# Microcontroller.net
KiCad netlist of a schematic drawn in Altium Designer
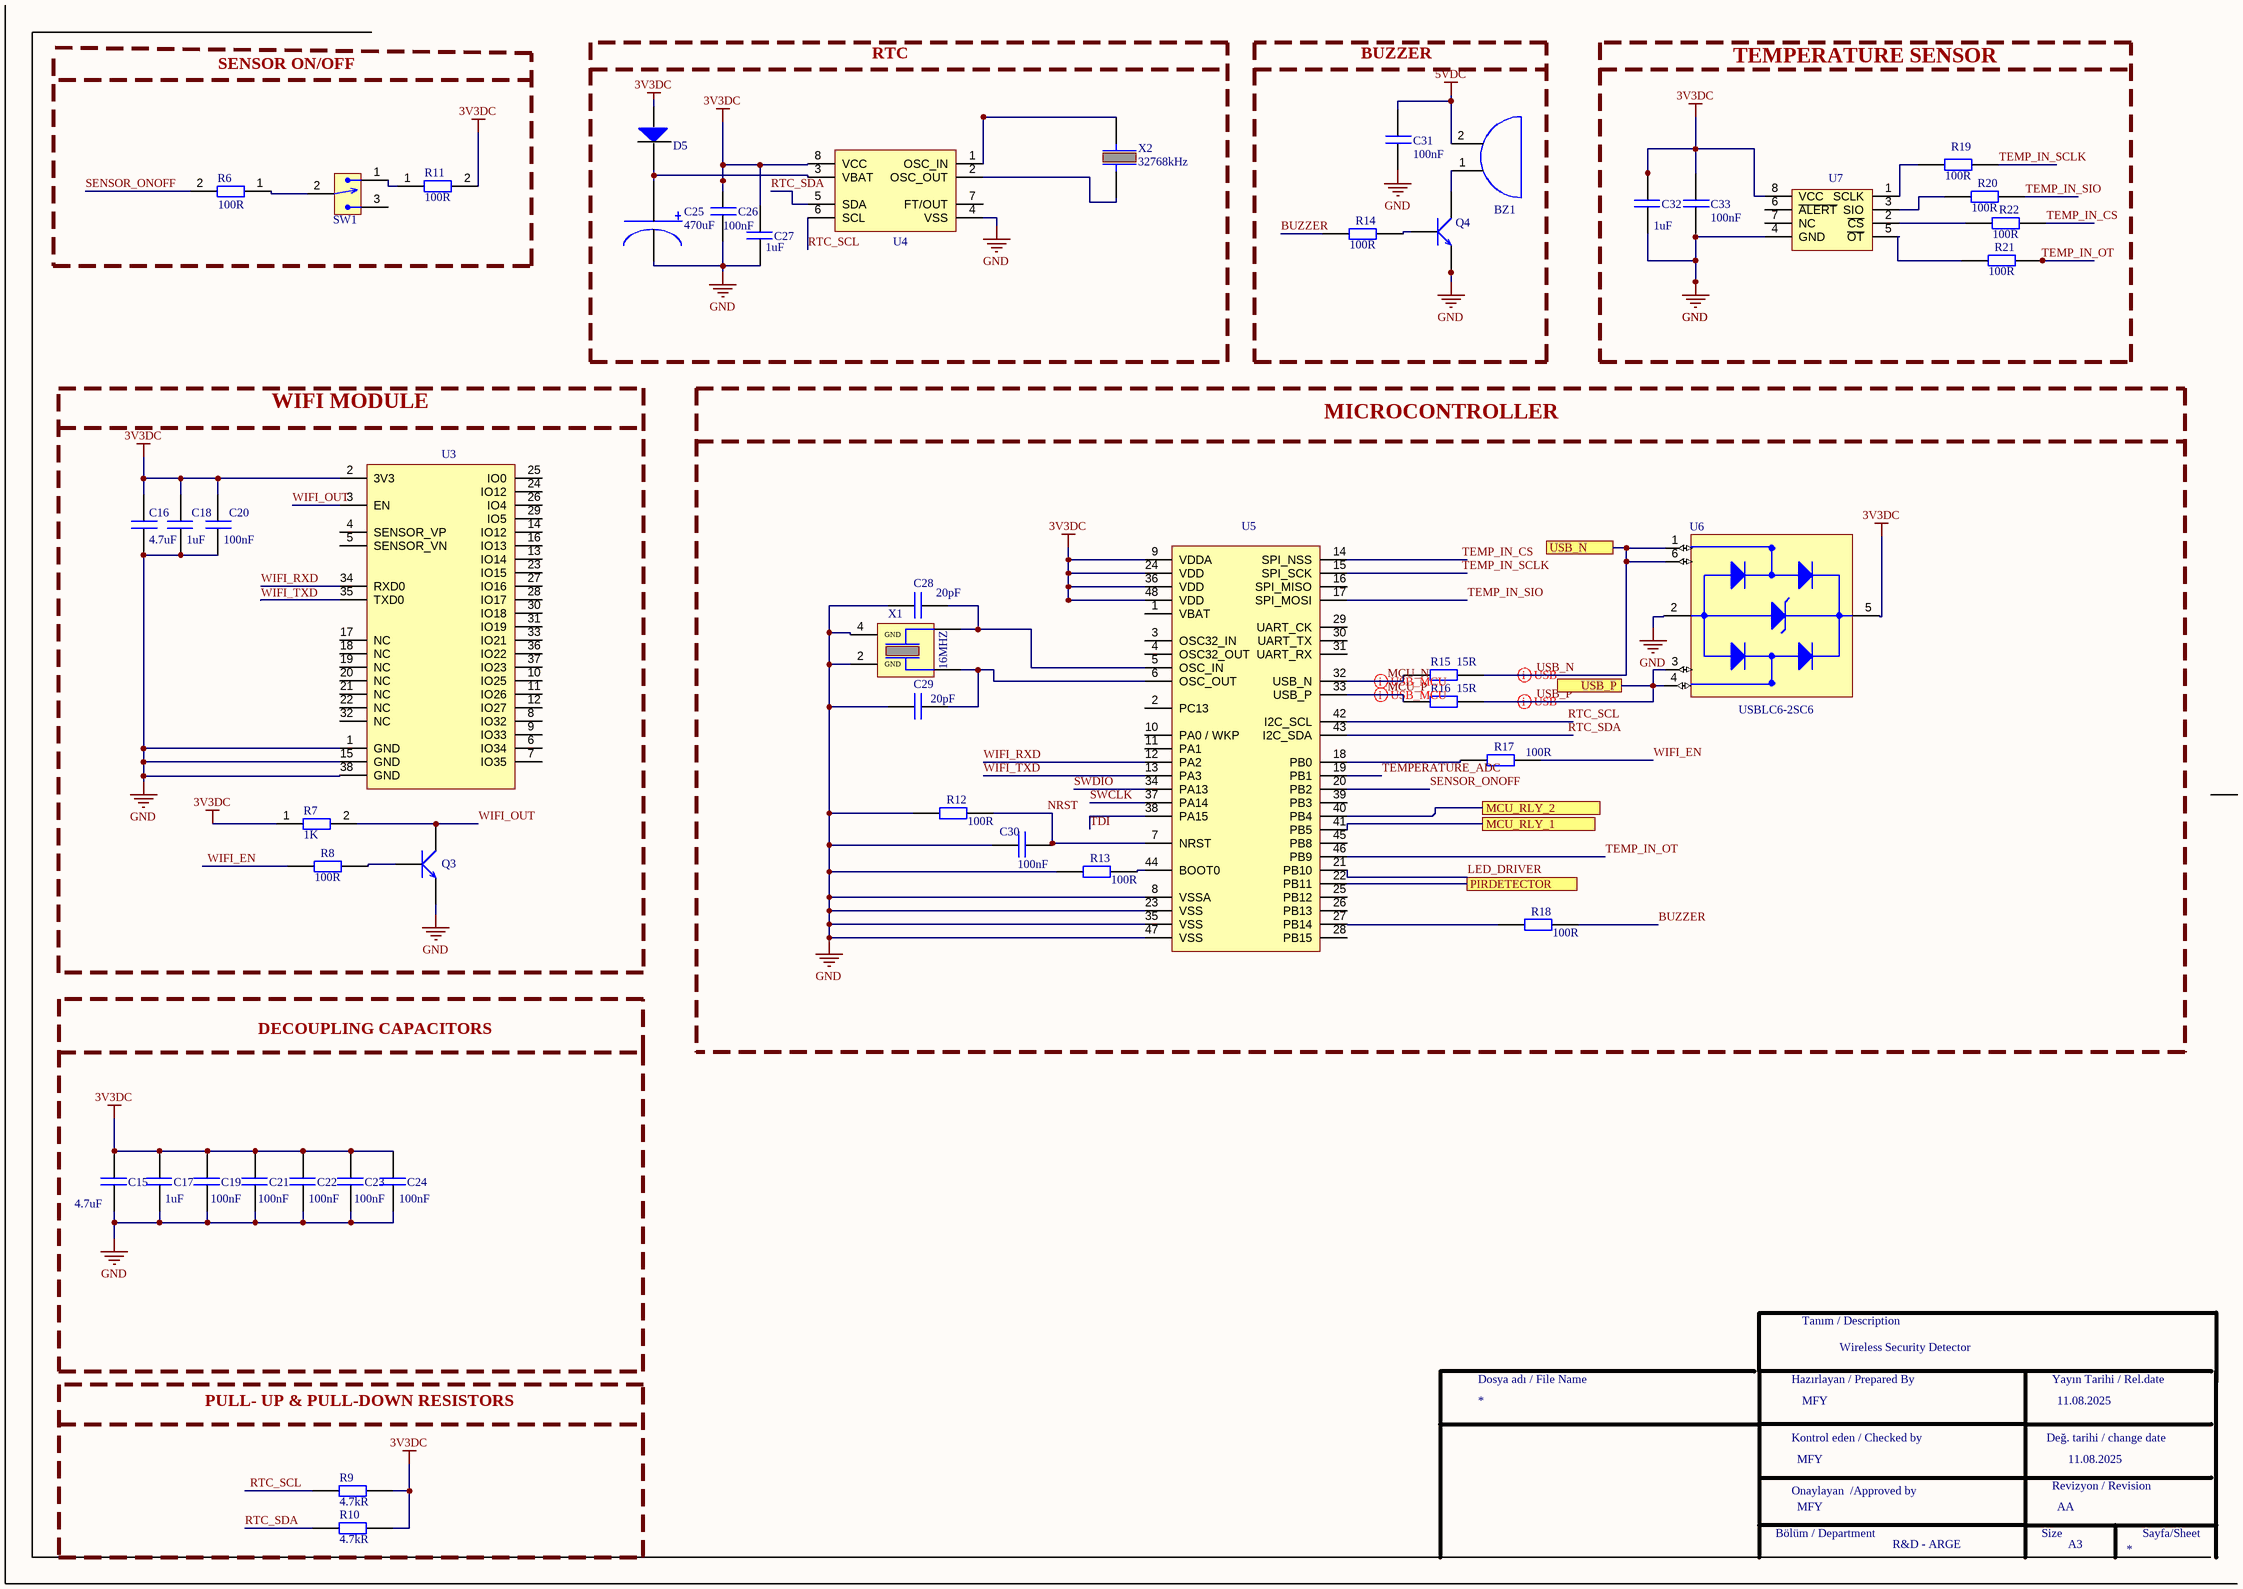
[diagram p0: Microcontroller.SchDoc]

(export (version "E")
  (design (tool "Eeschema 10.0.6"))
  (components
    (comp (ref "BZ1")
      (value "CMI-9605IC-0580T")
      (footprint "CMI-9605IC-0580T")
      (description "9.6 mm, 5 Vdc, 80 dB, Through Hole, Driving Circuit, Magnetic Audio Indicator Buzzer")
      (fields (field (name "MANUFACTURER") "Same Sky") (field (name "DESIGNED BY") "MFY"))
      (libsource (lib "Udemy_Library") (part "CMI-9605IC-0580T"))
    )
    (comp (ref "C15")
      (value "4.7uF")
      (footprint "CAP_0805")
      (fields
        (field (name "MANUFACTURER") "Samsung")
        (field (name "MANUFACTURER PART NUMBER") "CL21A475KAQNNNE")
      )
      (libsource (lib "Udemy_Library") (part "CAP CER 4.7uF 0805"))
    )
    (comp (ref "C16")
      (value "4.7uF")
      (footprint "CAP_0805")
      (fields
        (field (name "MANUFACTURER") "Samsung")
        (field (name "MANUFACTURER PART NUMBER") "CL21A475KAQNNNE")
      )
      (libsource (lib "Udemy_Library") (part "CAP CER 4.7uF 0805"))
    )
    (comp (ref "C17")
      (value "1uF")
      (footprint "CAP_0805")
      (fields
        (field (name "MANUFACTURER") "Samsung")
        (field (name "MANUFACTURER PART NUMBER") "CL21B105KBFNNNE")
      )
      (libsource (lib "Udemy_Library") (part "CAP CER 1uF 0805"))
    )
    (comp (ref "C18")
      (value "1uF")
      (footprint "CAP_0805")
      (fields
        (field (name "MANUFACTURER") "Samsung")
        (field (name "MANUFACTURER PART NUMBER") "CL21B105KBFNNNE")
      )
      (libsource (lib "Udemy_Library") (part "CAP CER 1uF 0805"))
    )
    (comp (ref "C19")
      (value "100nF")
      (footprint "CAP_0603")
      (description "CAP CER %10 100 nF 0603 Kemet")
      (fields
        (field (name "MANUFACTURER") "KEMET")
        (field (name "MANUFACTURER PART NUMBER") "C0603C104K5RACTU")
      )
      (libsource (lib "Udemy_Library") (part "CAP CER 100nF 0603"))
    )
    (comp (ref "C20")
      (value "100nF")
      (footprint "CAP_0805")
      (fields
        (field (name "MANUFACTURER") "Samsung")
        (field (name "MANUFACTURER PART NUMBER") "CL21B104KBCNNNC")
      )
      (libsource (lib "Udemy_Library") (part "CAP CER 100nF 0805"))
    )
    (comp (ref "C21")
      (value "100nF")
      (footprint "CAP_0603")
      (description "CAP CER %10 100 nF 0603 Kemet")
      (fields
        (field (name "MANUFACTURER") "KEMET")
        (field (name "MANUFACTURER PART NUMBER") "C0603C104K5RACTU")
      )
      (libsource (lib "Udemy_Library") (part "CAP CER 100nF 0603"))
    )
    (comp (ref "C22")
      (value "100nF")
      (footprint "CAP_0603")
      (description "CAP CER %10 100 nF 0603 Kemet")
      (fields
        (field (name "MANUFACTURER") "KEMET")
        (field (name "MANUFACTURER PART NUMBER") "C0603C104K5RACTU")
      )
      (libsource (lib "Udemy_Library") (part "CAP CER 100nF 0603"))
    )
    (comp (ref "C23")
      (value "100nF")
      (footprint "CAP_0603")
      (description "CAP CER %10 100 nF 0603 Kemet")
      (fields
        (field (name "MANUFACTURER") "KEMET")
        (field (name "MANUFACTURER PART NUMBER") "C0603C104K5RACTU")
      )
      (libsource (lib "Udemy_Library") (part "CAP CER 100nF 0603"))
    )
    (comp (ref "C24")
      (value "100nF")
      (footprint "CAP_0603")
      (description "CAP CER %10 100 nF 0603 Kemet")
      (fields
        (field (name "MANUFACTURER") "KEMET")
        (field (name "MANUFACTURER PART NUMBER") "C0603C104K5RACTU")
      )
      (libsource (lib "Udemy_Library") (part "CAP CER 100nF 0603"))
    )
    (comp (ref "C25")
      (value "470uF")
      (footprint "CAP_RADIAL_D10_P5")
      (fields
        (field (name "MANUFACTURER") "KEMET")
        (field (name "MANUFACTURER PART NUMBER") "ESH477M050AH4AA")
      )
      (libsource (lib "Udemy_Library") (part "CAP ALU ELEC 470uF 50V"))
    )
    (comp (ref "C26")
      (value "100nF")
      (footprint "CAP_0805")
      (fields
        (field (name "MANUFACTURER") "Samsung")
        (field (name "MANUFACTURER PART NUMBER") "CL21B104KBCNNNC")
      )
      (libsource (lib "Udemy_Library") (part "CAP CER 100nF 0805"))
    )
    (comp (ref "C27")
      (value "1uF")
      (footprint "CAP_0805")
      (fields
        (field (name "MANUFACTURER") "Samsung")
        (field (name "MANUFACTURER PART NUMBER") "CL21B105KBFNNNE")
      )
      (libsource (lib "Udemy_Library") (part "CAP CER 1uF 0805"))
    )
    (comp (ref "C28")
      (value "20pF")
      (footprint "CAP_0603")
      (fields
        (field (name "MANUFACTURER") "Samsung")
        (field (name "MANUFACTURER PART NUMBER") "CL10C200JB8NNNC")
      )
      (libsource (lib "Udemy_Library") (part "CAP CER 20 pF 0603"))
    )
    (comp (ref "C29")
      (value "20pF")
      (footprint "CAP_0603")
      (fields
        (field (name "MANUFACTURER") "Samsung")
        (field (name "MANUFACTURER PART NUMBER") "CL10C200JB8NNNC")
      )
      (libsource (lib "Udemy_Library") (part "CAP CER 20 pF 0603"))
    )
    (comp (ref "C30")
      (value "100nF")
      (footprint "CAP_0603")
      (description "CAP CER %10 100 nF 0603 Kemet")
      (fields
        (field (name "MANUFACTURER") "KEMET")
        (field (name "MANUFACTURER PART NUMBER") "C0603C104K5RACTU")
      )
      (libsource (lib "Udemy_Library") (part "CAP CER 100nF 0603"))
    )
    (comp (ref "C31")
      (value "100nF")
      (footprint "CAP_0805")
      (fields
        (field (name "MANUFACTURER") "Samsung")
        (field (name "MANUFACTURER PART NUMBER") "CL21B104KBCNNNC")
      )
      (libsource (lib "Udemy_Library") (part "CAP CER 100nF 0805"))
    )
    (comp (ref "C32")
      (value "1uF")
      (footprint "CAP_0805")
      (fields
        (field (name "MANUFACTURER") "Samsung")
        (field (name "MANUFACTURER PART NUMBER") "CL21B105KBFNNNE")
      )
      (libsource (lib "Udemy_Library") (part "CAP CER 1uF 0805"))
    )
    (comp (ref "C33")
      (value "100nF")
      (footprint "CAP_0805")
      (fields
        (field (name "MANUFACTURER") "Samsung")
        (field (name "MANUFACTURER PART NUMBER") "CL21B104KBCNNNC")
      )
      (libsource (lib "Udemy_Library") (part "CAP CER 100nF 0805"))
    )
    (comp (ref "D5")
      (value "1N4148WS")
      (footprint "SOD323F")
      (description "Rectifier Diode, 1 Phase, 1 Element, 0.15A, 100V V(RRM), Silicon")
      (fields (field (name "MANUFACTURER") "onsemi"))
      (libsource (lib "Udemy_Library") (part "1N4148WS"))
    )
    (comp (ref "Q3")
      (value "MMBT3904-7-F")
      (footprint "SOT23-F")
      (fields (field (name "MANUFACTURER") "Diodes Zetex") (field (name "DESIGNED BY") "MFY"))
      (libsource (lib "Udemy_Library") (part "MMBT3904-7-F"))
    )
    (comp (ref "Q4")
      (value "MMBT3904-7-F")
      (footprint "SOT23-F")
      (fields (field (name "MANUFACTURER") "Diodes Zetex") (field (name "DESIGNED BY") "MFY"))
      (libsource (lib "Udemy_Library") (part "MMBT3904-7-F"))
    )
    (comp (ref "R6")
      (value "100R")
      (footprint "RES_0603")
      (fields (field (name "Comment") "RES 100 OHM 0603"))
      (libsource (lib "") (part "RES 100 OHM 0603_2"))
    )
    (comp (ref "R7")
      (value "1K")
      (footprint "RES_0603")
      (fields (field (name "Comment") "RES 1K OHM 0603"))
      (libsource (lib "Udemy_Library") (part "RES 1K OHM 0603"))
    )
    (comp (ref "R8")
      (value "100R")
      (footprint "RES_0603")
      (fields (field (name "Comment") "RES 100 OHM 0603"))
      (libsource (lib "Udemy_Library") (part "RES 100 OHM 0603"))
    )
    (comp (ref "R9")
      (value "4.7kR")
      (footprint "RES_0603")
      (description "RES 4K7 Surface Mount, 0603")
      (fields
        (field (name "MANUFACTURER") "Yageo")
        (field (name "MANUFACTURER PART NUMBER") "RC0603JR-074K7L")
      )
      (libsource (lib "Udemy_Library") (part "RES 4.7K 0603"))
    )
    (comp (ref "R10")
      (value "4.7kR")
      (footprint "RES_0603")
      (description "RES 4K7 Surface Mount, 0603")
      (fields
        (field (name "MANUFACTURER") "Yageo")
        (field (name "MANUFACTURER PART NUMBER") "RC0603JR-074K7L")
      )
      (libsource (lib "Udemy_Library") (part "RES 4.7K 0603"))
    )
    (comp (ref "R11")
      (value "100R")
      (footprint "RES_0603")
      (fields (field (name "Comment") "RES 100 OHM 0603"))
      (libsource (lib "") (part "RES 100 OHM 0603_1"))
    )
    (comp (ref "R12")
      (value "100R")
      (footprint "RES_0603")
      (fields (field (name "Comment") "RES 100 OHM 0603"))
      (libsource (lib "Udemy_Library") (part "RES 100 OHM 0603"))
    )
    (comp (ref "R13")
      (value "100R")
      (footprint "RES_0603")
      (fields (field (name "Comment") "RES 100 OHM 0603"))
      (libsource (lib "Udemy_Library") (part "RES 100 OHM 0603"))
    )
    (comp (ref "R14")
      (value "100R")
      (footprint "RES_0603")
      (fields (field (name "Comment") "RES 100 OHM 0603"))
      (libsource (lib "Udemy_Library") (part "RES 100 OHM 0603"))
    )
    (comp (ref "R15")
      (value "15R")
      (footprint "RES_0603")
      (fields
        (field (name "MANUFACTURER") "Yageo")
        (field (name "MANUFACTURER PART NUMBER") "RC0603JR-0715RL")
        (field (name "TOLERANCE") "5%")
      )
      (libsource (lib "Udemy_Library") (part "RES 15R 0603"))
    )
    (comp (ref "R16")
      (value "15R")
      (footprint "RES_0603")
      (fields
        (field (name "MANUFACTURER") "Yageo")
        (field (name "MANUFACTURER PART NUMBER") "RC0603JR-0715RL")
        (field (name "TOLERANCE") "5%")
      )
      (libsource (lib "Udemy_Library") (part "RES 15R 0603"))
    )
    (comp (ref "R17")
      (value "100R")
      (footprint "RES_0603")
      (fields (field (name "Comment") "RES 100 OHM 0603"))
      (libsource (lib "Udemy_Library") (part "RES 100 OHM 0603"))
    )
    (comp (ref "R18")
      (value "100R")
      (footprint "RES_0603")
      (fields (field (name "Comment") "RES 100 OHM 0603"))
      (libsource (lib "Udemy_Library") (part "RES 100 OHM 0603"))
    )
    (comp (ref "R19")
      (value "100R")
      (footprint "RES_0603")
      (fields (field (name "Comment") "RES 100 OHM 0603"))
      (libsource (lib "Udemy_Library") (part "RES 100 OHM 0603"))
    )
    (comp (ref "R20")
      (value "100R")
      (footprint "RES_0603")
      (fields (field (name "Comment") "RES 100 OHM 0603"))
      (libsource (lib "Udemy_Library") (part "RES 100 OHM 0603"))
    )
    (comp (ref "R21")
      (value "100R")
      (footprint "RES_0603")
      (fields (field (name "Comment") "RES 100 OHM 0603"))
      (libsource (lib "Udemy_Library") (part "RES 100 OHM 0603"))
    )
    (comp (ref "R22")
      (value "100R")
      (footprint "RES_0603")
      (fields (field (name "Comment") "RES 100 OHM 0603"))
      (libsource (lib "Udemy_Library") (part "RES 100 OHM 0603"))
    )
    (comp (ref "SW1")
      (value "EG1215AA")
      (footprint "EG1215AA")
      (description "Slide Switch")
      (fields (field (name "MANUFACTURER") "E-Switch") (field (name "DESIGNED BY") "MFY"))
      (libsource (lib "Udemy_Library") (part "EG1215AA"))
    )
    (comp (ref "U3")
      (value "ESP32-WROOM-32E(4MB)")
      (footprint "ESP32-32E")
      (description "WiFi-Module 802.11/BT 2, 4-2, 5GHz 150Mb/s")
      (fields
        (field (name "MANUFACTURER") "Espressif Systems")
        (field (name "MANUFACTURER PART NUMBER") "ESP32-WROOM-32E-N4")
        (field (name "DESIGNED BY") "MFY")
      )
      (libsource (lib "Udemy_Library") (part "ESP32-WROOM-32E(4MB)"))
    )
    (comp (ref "U4")
      (value "M41T00SM6F")
      (footprint "SOIC8")
      (description "Real Time Clock, Volatile, 0 Timer(s), CMOS, PDSO8")
      (fields (field (name "MANUFACTURER") "STMicroelectronics") (field (name "DESIGNED BY") "MFY"))
      (libsource (lib "Udemy_Library") (part "M41T00SM6F"))
    )
    (comp (ref "U5")
      (value "STM32F103C6T6A")
      (footprint "LQFP-48")
      (description "RISC Microcontroller, 32-Bit, FLASH, CORTEX-M3 CPU, 72MHz, CMOS, LQFP48")
      (fields (field (name "MANUFACTURER") "STMicroelectronics") (field (name "DESIGNED BY") "MFY"))
      (libsource (lib "Udemy_Library") (part "STM32F103C6T6A"))
    )
    (comp (ref "U6")
      (value "USBLC6-2SC6")
      (footprint "SOT-23-6L")
      (description "Trans Voltage Suppressor Diode, 5V V(RWM), Unidirectional, 1 Element, Silicon")
      (fields (field (name "MANUFACTURER") "STMicroelectronics"))
      (libsource (lib "Udemy_Library") (part "USB PROTECTION"))
    )
    (comp (ref "U7")
      (value "MAX6662MSA+")
      (footprint "SOIC8")
      (description "Serial Switch/Digital Sensor, 12 Bit(s), 2.50Cel, BICMOS, Rectangular, 8 Pin, Surface Mount")
      (fields (field (name "MANUFACTURER") "Maxim"))
      (libsource (lib "Udemy_Library") (part "MAX6662MSA+"))
    )
    (comp (ref "X1")
      (value "ECS-160-20-30B-TR")
      (footprint "ECS")
      (description "Parallel - Fundamental Quartz Crystal, 16MHz Nom")
      (fields
        (field (name "MANUFACTURER") "ECS International")
        (field (name "OPERATING FREQUENCY-NOM") "16MHZ")
      )
      (libsource (lib "Udemy_Library") (part "CRYSTAL 16 MHz"))
    )
    (comp (ref "X2")
      (value "ABS05-32768KHZ-T")
      (footprint "ABS-05")
      (description "Parallel - Fundamental Quartz Crystal, 0.032768MHz Nom")
      (fields
        (field (name "MANUFACTURER") "Abracon")
        (field (name "MANUFACTURER PART NUMBER") "ABS05-32.768KHZ-T")
        (field (name "OPERATING FREQUENCY-NOM") "32768kHz")
      )
      (libsource (lib "Udemy_Library") (part "Crystal 32768KHz"))
    )
  )
  (nets
    (net (code "1") (name "/BUZZER") (class "Default")
      (node (ref "R14") (pin "1") (pinfunction "1_1") (pintype "passive"))
      (node (ref "R18") (pin "2") (pinfunction "2_2") (pintype "passive"))
    )
    (net (code "2") (name "/LED_DRIVER") (class "Default")
      (node (ref "U5") (pin "21") (pinfunction "PB10_21") (pintype "passive"))
    )
    (net (code "3") (name "/MCU_N") (class "Default")
      (node (ref "R15") (pin "1") (pinfunction "1_1") (pintype "passive"))
      (node (ref "U5") (pin "32") (pinfunction "USB_N_32") (pintype "passive"))
    )
    (net (code "4") (name "/MCU_P") (class "Default")
      (node (ref "R16") (pin "1") (pinfunction "1_1") (pintype "passive"))
      (node (ref "U5") (pin "33") (pinfunction "USB_P_33") (pintype "passive"))
    )
    (net (code "5") (name "/MCU_RLY_1") (class "Default")
      (node (ref "U5") (pin "41") (pinfunction "PB5_41") (pintype "passive"))
    )
    (net (code "6") (name "/MCU_RLY_2") (class "Default")
      (node (ref "U5") (pin "40") (pinfunction "PB4_40") (pintype "passive"))
    )
    (net (code "7") (name "/NRST") (class "Default")
      (node (ref "C30") (pin "2") (pinfunction "2_2") (pintype "passive"))
      (node (ref "R12") (pin "2") (pinfunction "2_2") (pintype "passive"))
      (node (ref "U5") (pin "7") (pinfunction "NRST_7") (pintype "passive"))
    )
    (net (code "8") (name "/PIRDETECTOR") (class "Default")
      (node (ref "U5") (pin "22") (pinfunction "PB11_22") (pintype "passive"))
    )
    (net (code "9") (name "/RTC_SCL") (class "Default")
      (node (ref "R9") (pin "1") (pinfunction "1_1") (pintype "passive"))
      (node (ref "U4") (pin "6") (pinfunction "SCL_6") (pintype "passive"))
      (node (ref "U5") (pin "42") (pinfunction "I2C_SCL_42") (pintype "passive"))
    )
    (net (code "10") (name "/RTC_SDA") (class "Default")
      (node (ref "R10") (pin "1") (pinfunction "1_1") (pintype "passive"))
      (node (ref "U4") (pin "5") (pinfunction "SDA_5") (pintype "passive"))
      (node (ref "U5") (pin "43") (pinfunction "I2C_SDA_43") (pintype "passive"))
    )
    (net (code "11") (name "/SENSOR_ONOFF") (class "Default")
      (node (ref "R6") (pin "2") (pinfunction "2_2") (pintype "passive"))
      (node (ref "U5") (pin "20") (pinfunction "PB2_20") (pintype "passive"))
    )
    (net (code "12") (name "/SWCLK") (class "Default")
      (node (ref "U5") (pin "37") (pinfunction "PA14_37") (pintype "passive"))
    )
    (net (code "13") (name "/SWDIO") (class "Default")
      (node (ref "U5") (pin "34") (pinfunction "PA13_34") (pintype "passive"))
    )
    (net (code "14") (name "/TDI") (class "Default")
      (node (ref "U5") (pin "38") (pinfunction "PA15_38") (pintype "passive"))
    )
    (net (code "15") (name "/TEMPERATURE_ADC") (class "Default")
      (node (ref "U5") (pin "19") (pinfunction "PB1_19") (pintype "passive"))
    )
    (net (code "16") (name "/TEMP_IN_CS") (class "Default")
      (node (ref "R22") (pin "2") (pinfunction "2_2") (pintype "passive"))
      (node (ref "U5") (pin "14") (pinfunction "SPI_NSS_14") (pintype "passive"))
    )
    (net (code "17") (name "/TEMP_IN_OT") (class "Default")
      (node (ref "R21") (pin "2") (pinfunction "2_2") (pintype "passive"))
      (node (ref "U5") (pin "46") (pinfunction "PB9_46") (pintype "passive"))
    )
    (net (code "18") (name "/TEMP_IN_SCLK") (class "Default")
      (node (ref "R19") (pin "2") (pinfunction "2_2") (pintype "passive"))
      (node (ref "U5") (pin "15") (pinfunction "SPI_SCK_15") (pintype "passive"))
    )
    (net (code "19") (name "/TEMP_IN_SIO") (class "Default")
      (node (ref "R20") (pin "2") (pinfunction "2_2") (pintype "passive"))
      (node (ref "U5") (pin "17") (pinfunction "SPI_MOSI_17") (pintype "passive"))
    )
    (net (code "20") (name "/USB_N") (class "Default")
      (node (ref "R15") (pin "2") (pinfunction "2_2") (pintype "passive"))
      (node (ref "U6") (pin "1") (pinfunction "I/O1_IN_1") (pintype "bidirectional"))
      (node (ref "U6") (pin "6") (pinfunction "I/O1_OUT_6") (pintype "bidirectional"))
    )
    (net (code "21") (name "/USB_P") (class "Default")
      (node (ref "R16") (pin "2") (pinfunction "2_2") (pintype "passive"))
      (node (ref "U6") (pin "3") (pinfunction "I/O2_IN_3") (pintype "bidirectional"))
      (node (ref "U6") (pin "4") (pinfunction "I/O2_OUT_4") (pintype "bidirectional"))
    )
    (net (code "22") (name "/WIFI_EN") (class "Default")
      (node (ref "R17") (pin "2") (pinfunction "2_2") (pintype "passive"))
      (node (ref "R8") (pin "1") (pinfunction "1_1") (pintype "passive"))
    )
    (net (code "23") (name "/WIFI_OUT") (class "Default")
      (node (ref "Q3") (pin "3") (pinfunction "C_3") (pintype "passive"))
      (node (ref "R7") (pin "2") (pinfunction "2_2") (pintype "passive"))
      (node (ref "U3") (pin "3") (pinfunction "EN_3") (pintype "passive"))
    )
    (net (code "24") (name "/WIFI_RXD") (class "Default")
      (node (ref "U3") (pin "34") (pinfunction "RXD0_34") (pintype "passive"))
      (node (ref "U5") (pin "12") (pinfunction "PA2_12") (pintype "passive"))
    )
    (net (code "25") (name "/WIFI_TXD") (class "Default")
      (node (ref "U3") (pin "35") (pinfunction "TXD0_35") (pintype "passive"))
      (node (ref "U5") (pin "13") (pinfunction "PA3_13") (pintype "passive"))
    )
    (net (code "26") (name "3V3DC") (class "Default")
      (node (ref "C15") (pin "2") (pinfunction "2_2") (pintype "passive"))
      (node (ref "C16") (pin "1") (pinfunction "1_1") (pintype "passive"))
      (node (ref "C17") (pin "2") (pinfunction "2_2") (pintype "passive"))
      (node (ref "C18") (pin "2") (pinfunction "2_2") (pintype "passive"))
      (node (ref "C19") (pin "2") (pinfunction "2_2") (pintype "passive"))
      (node (ref "C20") (pin "1") (pinfunction "1_1") (pintype "passive"))
      (node (ref "C21") (pin "2") (pinfunction "2_2") (pintype "passive"))
      (node (ref "C22") (pin "2") (pinfunction "2_2") (pintype "passive"))
      (node (ref "C23") (pin "2") (pinfunction "2_2") (pintype "passive"))
      (node (ref "C24") (pin "2") (pinfunction "2_2") (pintype "passive"))
      (node (ref "C26") (pin "1") (pinfunction "1_1") (pintype "passive"))
      (node (ref "C27") (pin "2") (pinfunction "2_2") (pintype "passive"))
      (node (ref "C32") (pin "2") (pinfunction "2_2") (pintype "passive"))
      (node (ref "C33") (pin "1") (pinfunction "1_1") (pintype "passive"))
      (node (ref "D5") (pin "2") (pinfunction "2_2") (pintype "passive"))
      (node (ref "R10") (pin "2") (pinfunction "2_2") (pintype "passive"))
      (node (ref "R11") (pin "2") (pinfunction "2_2") (pintype "passive"))
      (node (ref "R7") (pin "1") (pinfunction "1_1") (pintype "passive"))
      (node (ref "R9") (pin "2") (pinfunction "2_2") (pintype "passive"))
      (node (ref "U3") (pin "2") (pinfunction "3V3_2") (pintype "passive"))
      (node (ref "U4") (pin "8") (pinfunction "VCC_8") (pintype "passive"))
      (node (ref "U5") (pin "24") (pinfunction "VDD_24") (pintype "passive"))
      (node (ref "U5") (pin "36") (pinfunction "VDD_36") (pintype "passive"))
      (node (ref "U5") (pin "48") (pinfunction "VDD_48") (pintype "passive"))
      (node (ref "U5") (pin "9") (pinfunction "VDDA_9") (pintype "passive"))
      (node (ref "U6") (pin "5") (pinfunction "VBUS_5") (pintype "power_in"))
      (node (ref "U7") (pin "8") (pinfunction "VCC_8") (pintype "passive"))
    )
    (net (code "27") (name "5VDC") (class "Default")
      (node (ref "BZ1") (pin "2") (pinfunction "2_2") (pintype "passive"))
      (node (ref "C31") (pin "1") (pinfunction "1_1") (pintype "passive"))
    )
    (net (code "28") (name "GND") (class "Default")
      (node (ref "C15") (pin "1") (pinfunction "1_1") (pintype "passive"))
      (node (ref "C16") (pin "2") (pinfunction "2_2") (pintype "passive"))
      (node (ref "C17") (pin "1") (pinfunction "1_1") (pintype "passive"))
      (node (ref "C18") (pin "1") (pinfunction "1_1") (pintype "passive"))
      (node (ref "C19") (pin "1") (pinfunction "1_1") (pintype "passive"))
      (node (ref "C20") (pin "2") (pinfunction "2_2") (pintype "passive"))
      (node (ref "C21") (pin "1") (pinfunction "1_1") (pintype "passive"))
      (node (ref "C22") (pin "1") (pinfunction "1_1") (pintype "passive"))
      (node (ref "C23") (pin "1") (pinfunction "1_1") (pintype "passive"))
      (node (ref "C24") (pin "1") (pinfunction "1_1") (pintype "passive"))
      (node (ref "C25") (pin "2") (pinfunction "2_2") (pintype "passive"))
      (node (ref "C26") (pin "2") (pinfunction "2_2") (pintype "passive"))
      (node (ref "C27") (pin "1") (pinfunction "1_1") (pintype "passive"))
      (node (ref "C28") (pin "1") (pinfunction "1_1") (pintype "passive"))
      (node (ref "C29") (pin "1") (pinfunction "1_1") (pintype "passive"))
      (node (ref "C30") (pin "1") (pinfunction "1_1") (pintype "passive"))
      (node (ref "C31") (pin "2") (pinfunction "2_2") (pintype "passive"))
      (node (ref "C32") (pin "1") (pinfunction "1_1") (pintype "passive"))
      (node (ref "C33") (pin "2") (pinfunction "2_2") (pintype "passive"))
      (node (ref "Q3") (pin "2") (pinfunction "E_2") (pintype "passive"))
      (node (ref "Q4") (pin "2") (pinfunction "E_2") (pintype "passive"))
      (node (ref "R12") (pin "1") (pinfunction "1_1") (pintype "passive"))
      (node (ref "R13") (pin "1") (pinfunction "1_1") (pintype "passive"))
      (node (ref "U3") (pin "1") (pinfunction "GND_1") (pintype "passive"))
      (node (ref "U3") (pin "15") (pinfunction "GND_15") (pintype "passive"))
      (node (ref "U3") (pin "38") (pinfunction "GND_38") (pintype "passive"))
      (node (ref "U4") (pin "4") (pinfunction "VSS_4") (pintype "passive"))
      (node (ref "U5") (pin "23") (pinfunction "VSS_23") (pintype "passive"))
      (node (ref "U5") (pin "35") (pinfunction "VSS_35") (pintype "passive"))
      (node (ref "U5") (pin "47") (pinfunction "VSS_47") (pintype "passive"))
      (node (ref "U5") (pin "8") (pinfunction "VSSA_8") (pintype "passive"))
      (node (ref "U6") (pin "2") (pinfunction "GND_2") (pintype "power_in"))
      (node (ref "U7") (pin "4") (pinfunction "GND_4") (pintype "passive"))
      (node (ref "X1") (pin "2") (pinfunction "GND_2") (pintype "passive"))
      (node (ref "X1") (pin "4") (pinfunction "GND_4") (pintype "passive"))
    )
    (net (code "29") (name "Net-(Q3-B)") (class "Default")
      (node (ref "Q3") (pin "1") (pinfunction "B_1") (pintype "passive"))
      (node (ref "R8") (pin "2") (pinfunction "2_2") (pintype "passive"))
    )
    (net (code "30") (name "Net-(Q4-B)") (class "Default")
      (node (ref "Q4") (pin "1") (pinfunction "B_1") (pintype "passive"))
      (node (ref "R14") (pin "2") (pinfunction "2_2") (pintype "passive"))
    )
    (net (code "31") (name "Net-(Q4-C)") (class "Default")
      (node (ref "BZ1") (pin "1") (pinfunction "1_1") (pintype "passive"))
      (node (ref "Q4") (pin "3") (pinfunction "C_3") (pintype "passive"))
    )
    (net (code "32") (name "Net-(R6-Pad1)") (class "Default")
      (node (ref "R6") (pin "1") (pinfunction "1_1") (pintype "passive"))
      (node (ref "SW1") (pin "2") (pinfunction "2_2") (pintype "passive"))
    )
    (net (code "33") (name "Net-(R11-Pad1)") (class "Default")
      (node (ref "R11") (pin "1") (pinfunction "1_1") (pintype "passive"))
      (node (ref "SW1") (pin "1") (pinfunction "1_1") (pintype "passive"))
    )
    (net (code "34") (name "Net-(U4-OSC_IN)") (class "Default")
      (node (ref "U4") (pin "1") (pinfunction "OSC_IN_1") (pintype "passive"))
      (node (ref "X2") (pin "1") (pinfunction "1_1") (pintype "passive"))
    )
    (net (code "35") (name "Net-(U4-OSC_OUT)") (class "Default")
      (node (ref "U4") (pin "2") (pinfunction "OSC_OUT_2") (pintype "passive"))
      (node (ref "X2") (pin "2") (pinfunction "2_2") (pintype "passive"))
    )
    (net (code "36") (name "Net-(U4-VBAT)") (class "Default")
      (node (ref "C25") (pin "1") (pinfunction "1_1") (pintype "passive"))
      (node (ref "D5") (pin "1") (pinfunction "1_1") (pintype "passive"))
      (node (ref "U4") (pin "3") (pinfunction "VBAT_3") (pintype "passive"))
    )
    (net (code "37") (name "Net-(U5-BOOT0)") (class "Default")
      (node (ref "R13") (pin "2") (pinfunction "2_2") (pintype "passive"))
      (node (ref "U5") (pin "44") (pinfunction "BOOT0_44") (pintype "passive"))
    )
    (net (code "38") (name "Net-(U5-OSC_IN)") (class "Default")
      (node (ref "C28") (pin "2") (pinfunction "2_2") (pintype "passive"))
      (node (ref "U5") (pin "5") (pinfunction "OSC_IN_5") (pintype "passive"))
      (node (ref "X1") (pin "3") (pinfunction "3_3") (pintype "passive"))
    )
    (net (code "39") (name "Net-(U5-OSC_OUT)") (class "Default")
      (node (ref "C29") (pin "2") (pinfunction "2_2") (pintype "passive"))
      (node (ref "U5") (pin "6") (pinfunction "OSC_OUT_6") (pintype "passive"))
      (node (ref "X1") (pin "1") (pinfunction "1_1") (pintype "passive"))
    )
    (net (code "40") (name "Net-(U5-PB0)") (class "Default")
      (node (ref "R17") (pin "1") (pinfunction "1_1") (pintype "passive"))
      (node (ref "U5") (pin "18") (pinfunction "PB0_18") (pintype "passive"))
    )
    (net (code "41") (name "Net-(U5-PB14)") (class "Default")
      (node (ref "R18") (pin "1") (pinfunction "1_1") (pintype "passive"))
      (node (ref "U5") (pin "27") (pinfunction "PB14_27") (pintype "passive"))
    )
    (net (code "42") (name "Net-(U7-SCLK)") (class "Default")
      (node (ref "R19") (pin "1") (pinfunction "1_1") (pintype "passive"))
      (node (ref "U7") (pin "1") (pinfunction "SCLK_1") (pintype "passive"))
    )
    (net (code "43") (name "Net-(U7-SIO)") (class "Default")
      (node (ref "R20") (pin "1") (pinfunction "1_1") (pintype "passive"))
      (node (ref "U7") (pin "3") (pinfunction "SIO_3") (pintype "passive"))
    )
    (net (code "44") (name "Net-(U7-~{CS})") (class "Default")
      (node (ref "R22") (pin "1") (pinfunction "1_1") (pintype "passive"))
      (node (ref "U7") (pin "2") (pinfunction "~{CS}_2") (pintype "passive"))
    )
    (net (code "45") (name "Net-(U7-~{OT})") (class "Default")
      (node (ref "R21") (pin "1") (pinfunction "1_1") (pintype "passive"))
      (node (ref "U7") (pin "5") (pinfunction "~{OT}_5") (pintype "passive"))
    )
    (net (code "46") (name "unconnected-(SW1-Pad3)") (class "Default")
      (node (ref "SW1") (pin "3") (pinfunction "3_3") (pintype "passive"))
    )
    (net (code "47") (name "unconnected-(U3-IO0-Pad25)") (class "Default")
      (node (ref "U3") (pin "25") (pinfunction "IO0_25") (pintype "passive"))
    )
    (net (code "48") (name "unconnected-(U3-IO4-Pad26)") (class "Default")
      (node (ref "U3") (pin "26") (pinfunction "IO4_26") (pintype "passive"))
    )
    (net (code "49") (name "unconnected-(U3-IO5-Pad29)") (class "Default")
      (node (ref "U3") (pin "29") (pinfunction "IO5_29") (pintype "passive"))
    )
    (net (code "50") (name "unconnected-(U3-IO12-Pad14)") (class "Default")
      (node (ref "U3") (pin "14") (pinfunction "IO12_14") (pintype "passive"))
    )
    (net (code "51") (name "unconnected-(U3-IO12-Pad24)") (class "Default")
      (node (ref "U3") (pin "24") (pinfunction "IO12_24") (pintype "passive"))
    )
    (net (code "52") (name "unconnected-(U3-IO13-Pad16)") (class "Default")
      (node (ref "U3") (pin "16") (pinfunction "IO13_16") (pintype "passive"))
    )
    (net (code "53") (name "unconnected-(U3-IO14-Pad13)") (class "Default")
      (node (ref "U3") (pin "13") (pinfunction "IO14_13") (pintype "passive"))
    )
    (net (code "54") (name "unconnected-(U3-IO15-Pad23)") (class "Default")
      (node (ref "U3") (pin "23") (pinfunction "IO15_23") (pintype "passive"))
    )
    (net (code "55") (name "unconnected-(U3-IO16-Pad27)") (class "Default")
      (node (ref "U3") (pin "27") (pinfunction "IO16_27") (pintype "passive"))
    )
    (net (code "56") (name "unconnected-(U3-IO17-Pad28)") (class "Default")
      (node (ref "U3") (pin "28") (pinfunction "IO17_28") (pintype "passive"))
    )
    (net (code "57") (name "unconnected-(U3-IO18-Pad30)") (class "Default")
      (node (ref "U3") (pin "30") (pinfunction "IO18_30") (pintype "passive"))
    )
    (net (code "58") (name "unconnected-(U3-IO19-Pad31)") (class "Default")
      (node (ref "U3") (pin "31") (pinfunction "IO19_31") (pintype "passive"))
    )
    (net (code "59") (name "unconnected-(U3-IO21-Pad33)") (class "Default")
      (node (ref "U3") (pin "33") (pinfunction "IO21_33") (pintype "passive"))
    )
    (net (code "60") (name "unconnected-(U3-IO22-Pad36)") (class "Default")
      (node (ref "U3") (pin "36") (pinfunction "IO22_36") (pintype "passive"))
    )
    (net (code "61") (name "unconnected-(U3-IO23-Pad37)") (class "Default")
      (node (ref "U3") (pin "37") (pinfunction "IO23_37") (pintype "passive"))
    )
    (net (code "62") (name "unconnected-(U3-IO25-Pad10)") (class "Default")
      (node (ref "U3") (pin "10") (pinfunction "IO25_10") (pintype "passive"))
    )
    (net (code "63") (name "unconnected-(U3-IO26-Pad11)") (class "Default")
      (node (ref "U3") (pin "11") (pinfunction "IO26_11") (pintype "passive"))
    )
    (net (code "64") (name "unconnected-(U3-IO27-Pad12)") (class "Default")
      (node (ref "U3") (pin "12") (pinfunction "IO27_12") (pintype "passive"))
    )
    (net (code "65") (name "unconnected-(U3-IO32-Pad8)") (class "Default")
      (node (ref "U3") (pin "8") (pinfunction "IO32_8") (pintype "passive"))
    )
    (net (code "66") (name "unconnected-(U3-IO33-Pad9)") (class "Default")
      (node (ref "U3") (pin "9") (pinfunction "IO33_9") (pintype "passive"))
    )
    (net (code "67") (name "unconnected-(U3-IO34-Pad6)") (class "Default")
      (node (ref "U3") (pin "6") (pinfunction "IO34_6") (pintype "passive"))
    )
    (net (code "68") (name "unconnected-(U3-IO35-Pad7)") (class "Default")
      (node (ref "U3") (pin "7") (pinfunction "IO35_7") (pintype "passive"))
    )
    (net (code "69") (name "unconnected-(U3-NC-Pad17)") (class "Default")
      (node (ref "U3") (pin "17") (pinfunction "NC_17") (pintype "passive"))
    )
    (net (code "70") (name "unconnected-(U3-NC-Pad18)") (class "Default")
      (node (ref "U3") (pin "18") (pinfunction "NC_18") (pintype "passive"))
    )
    (net (code "71") (name "unconnected-(U3-NC-Pad19)") (class "Default")
      (node (ref "U3") (pin "19") (pinfunction "NC_19") (pintype "passive"))
    )
    (net (code "72") (name "unconnected-(U3-NC-Pad20)") (class "Default")
      (node (ref "U3") (pin "20") (pinfunction "NC_20") (pintype "passive"))
    )
    (net (code "73") (name "unconnected-(U3-NC-Pad21)") (class "Default")
      (node (ref "U3") (pin "21") (pinfunction "NC_21") (pintype "passive"))
    )
    (net (code "74") (name "unconnected-(U3-NC-Pad22)") (class "Default")
      (node (ref "U3") (pin "22") (pinfunction "NC_22") (pintype "passive"))
    )
    (net (code "75") (name "unconnected-(U3-NC-Pad32)") (class "Default")
      (node (ref "U3") (pin "32") (pinfunction "NC_32") (pintype "passive"))
    )
    (net (code "76") (name "unconnected-(U3-SENSOR_VN-Pad5)") (class "Default")
      (node (ref "U3") (pin "5") (pinfunction "SENSOR_VN_5") (pintype "passive"))
    )
    (net (code "77") (name "unconnected-(U3-SENSOR_VP-Pad4)") (class "Default")
      (node (ref "U3") (pin "4") (pinfunction "SENSOR_VP_4") (pintype "passive"))
    )
    (net (code "78") (name "unconnected-(U4-FT{slash}OUT-Pad7)") (class "Default")
      (node (ref "U4") (pin "7") (pinfunction "FT/OUT_7") (pintype "passive"))
    )
    (net (code "79") (name "unconnected-(U5-OSC32_IN-Pad3)") (class "Default")
      (node (ref "U5") (pin "3") (pinfunction "OSC32_IN_3") (pintype "passive"))
    )
    (net (code "80") (name "unconnected-(U5-OSC32_OUT-Pad4)") (class "Default")
      (node (ref "U5") (pin "4") (pinfunction "OSC32_OUT_4") (pintype "passive"))
    )
    (net (code "81") (name "unconnected-(U5-PA0_{slash}_WKP-Pad10)") (class "Default")
      (node (ref "U5") (pin "10") (pinfunction "PA0_/_WKP_10") (pintype "passive"))
    )
    (net (code "82") (name "unconnected-(U5-PA1-Pad11)") (class "Default")
      (node (ref "U5") (pin "11") (pinfunction "PA1_11") (pintype "passive"))
    )
    (net (code "83") (name "unconnected-(U5-PB3-Pad39)") (class "Default")
      (node (ref "U5") (pin "39") (pinfunction "PB3_39") (pintype "passive"))
    )
    (net (code "84") (name "unconnected-(U5-PB8-Pad45)") (class "Default")
      (node (ref "U5") (pin "45") (pinfunction "PB8_45") (pintype "passive"))
    )
    (net (code "85") (name "unconnected-(U5-PB12-Pad25)") (class "Default")
      (node (ref "U5") (pin "25") (pinfunction "PB12_25") (pintype "passive"))
    )
    (net (code "86") (name "unconnected-(U5-PB13-Pad26)") (class "Default")
      (node (ref "U5") (pin "26") (pinfunction "PB13_26") (pintype "passive"))
    )
    (net (code "87") (name "unconnected-(U5-PB15-Pad28)") (class "Default")
      (node (ref "U5") (pin "28") (pinfunction "PB15_28") (pintype "passive"))
    )
    (net (code "88") (name "unconnected-(U5-PC13-Pad2)") (class "Default")
      (node (ref "U5") (pin "2") (pinfunction "PC13_2") (pintype "passive"))
    )
    (net (code "89") (name "unconnected-(U5-SPI_MISO-Pad16)") (class "Default")
      (node (ref "U5") (pin "16") (pinfunction "SPI_MISO_16") (pintype "passive"))
    )
    (net (code "90") (name "unconnected-(U5-UART_CK-Pad29)") (class "Default")
      (node (ref "U5") (pin "29") (pinfunction "UART_CK_29") (pintype "passive"))
    )
    (net (code "91") (name "unconnected-(U5-UART_RX-Pad31)") (class "Default")
      (node (ref "U5") (pin "31") (pinfunction "UART_RX_31") (pintype "passive"))
    )
    (net (code "92") (name "unconnected-(U5-UART_TX-Pad30)") (class "Default")
      (node (ref "U5") (pin "30") (pinfunction "UART_TX_30") (pintype "passive"))
    )
    (net (code "93") (name "unconnected-(U5-VBAT-Pad1)") (class "Default")
      (node (ref "U5") (pin "1") (pinfunction "VBAT_1") (pintype "passive"))
    )
    (net (code "94") (name "unconnected-(U7-NC-Pad7)") (class "Default")
      (node (ref "U7") (pin "7") (pinfunction "NC_7") (pintype "passive"))
    )
    (net (code "95") (name "unconnected-(U7-~{ALERT}-Pad6)") (class "Default")
      (node (ref "U7") (pin "6") (pinfunction "~{ALERT}_6") (pintype "passive"))
    )
  )
)
